# Main.net
KiCad netlist of a schematic drawn in Altium Designer
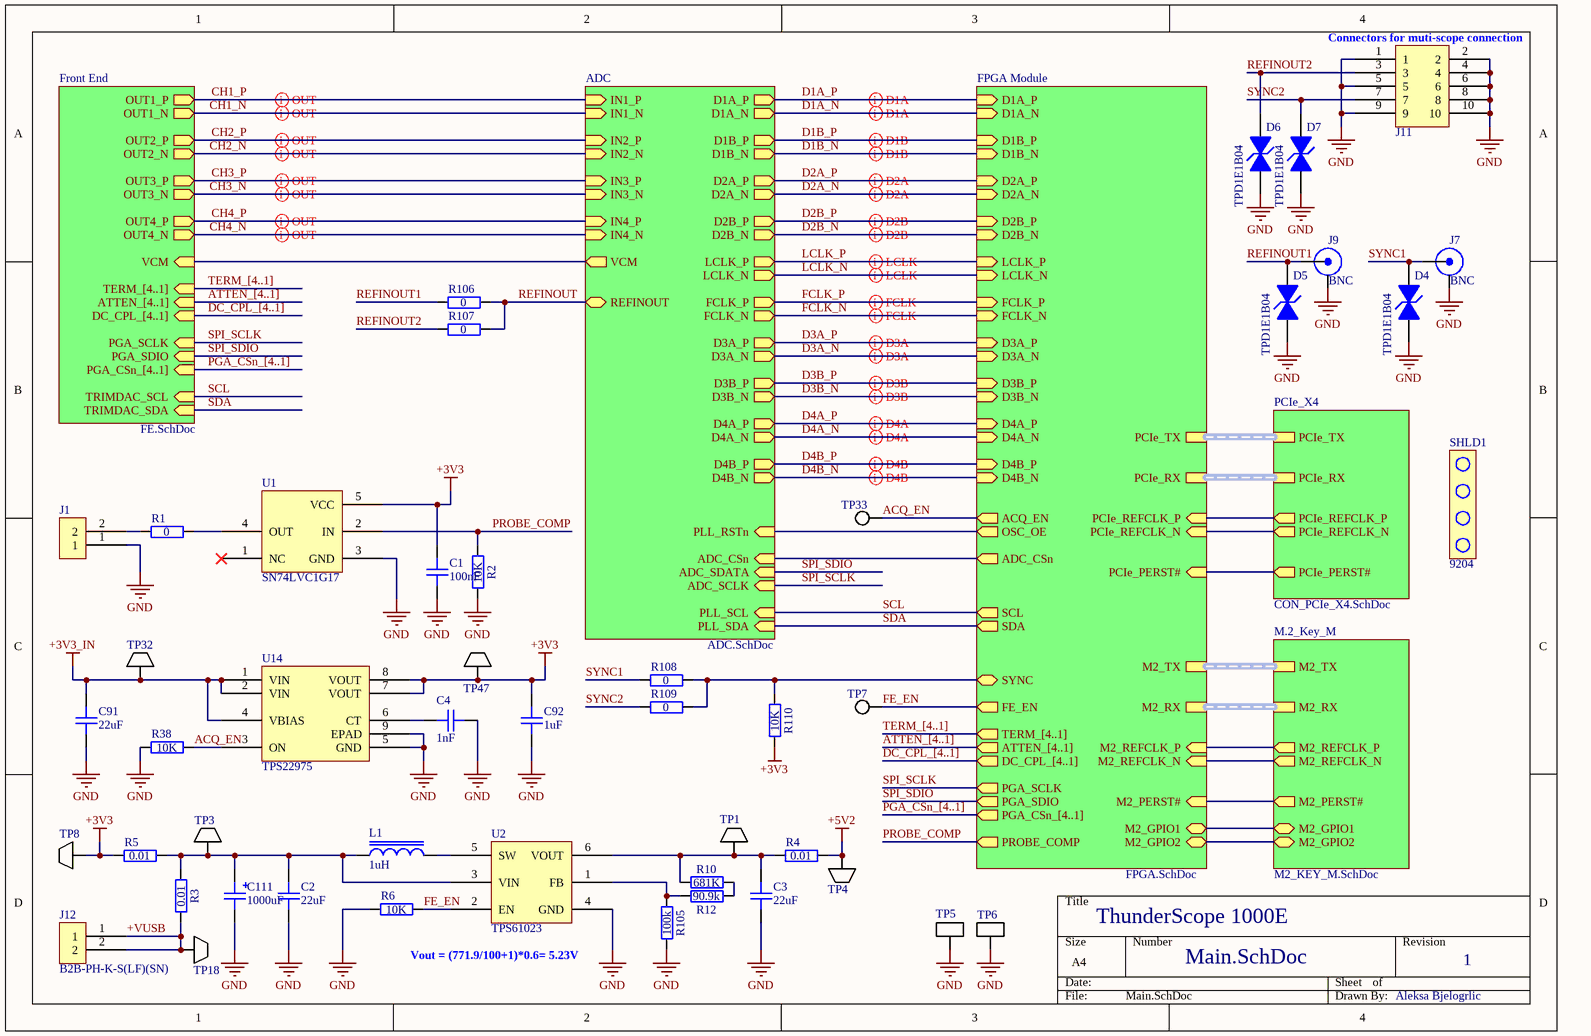
[diagram p0: Main.SchDoc]

(export (version "E")
  (design (tool "Eeschema 10.0.6"))
  (components
    (comp (ref "C1")
      (value "100nF")
      (footprint "GEN_C_0402")
      (libsource (lib "DSO") (part "CAP 100nF 16V X7R 0402"))
    )
    (comp (ref "C2")
      (value "22uF")
      (footprint "GEN_C_0805")
      (libsource (lib "DSO") (part "CAP 22uF 25V X5R 0805"))
    )
    (comp (ref "C3")
      (value "22uF")
      (footprint "GEN_C_0805")
      (libsource (lib "DSO") (part "CAP 22uF 25V X5R 0805"))
    )
    (comp (ref "C4")
      (value "1nF")
      (footprint "GEN_C_0402")
      (libsource (lib "DSO") (part "CAP 1nF 50V C0G 0402"))
    )
    (comp (ref "C91")
      (value "22uF")
      (footprint "GEN_C_0805")
      (libsource (lib "DSO") (part "CAP 22uF 25V X5R 0805"))
    )
    (comp (ref "C92")
      (value "1uF")
      (footprint "GEN_C_0402")
      (libsource (lib "DSO") (part "CAP 1uF 25V X5R 0402"))
    )
    (comp (ref "C111")
      (value "1000uF")
      (footprint "GEN_C_POLAR_10mm")
      (libsource (lib "DSO") (part "CAP 1000uF 16V 10mm Dia"))
    )
    (comp (ref "D4")
      (value "TPD1E1B04")
      (footprint "TI_X1SON_DPY0002A")
      (libsource (lib "DSO") (part "TVS TPD1E1B04"))
    )
    (comp (ref "D5")
      (value "TPD1E1B04")
      (footprint "TI_X1SON_DPY0002A")
      (libsource (lib "DSO") (part "TVS TPD1E1B04"))
    )
    (comp (ref "D6")
      (value "TPD1E1B04")
      (footprint "TI_X1SON_DPY0002A")
      (libsource (lib "DSO") (part "TVS TPD1E1B04"))
    )
    (comp (ref "D7")
      (value "TPD1E1B04")
      (footprint "TI_X1SON_DPY0002A")
      (libsource (lib "DSO") (part "TVS TPD1E1B04"))
    )
    (comp (ref "J1")
      (value "TSW-101-08-F-D-RA")
      (footprint "GEN_2.54mm_1x2_Pin_TH_RA")
      (libsource (lib "DSO") (part "CONN 2.54mm 2 Pin TH RA"))
    )
    (comp (ref "J7") (value "BNC") (footprint "MOL_0731000105") (libsource (lib "DSO") (part "BNC JACK R/A")))
    (comp (ref "J9") (value "BNC") (footprint "MOL_0731000105") (libsource (lib "DSO") (part "BNC JACK R/A")))
    (comp (ref "J11")
      (value "1.27mm 6 Pin TH")
      (footprint "GEN_1.27mm_2x5_Pin_TH_RA")
      (libsource (lib "DSO") (part "CONN 1.27mm 2x5 Pin TH RA"))
    )
    (comp (ref "J12")
      (value "B2B-PH-K-S(LF)(SN)")
      (footprint "JST_B2B-PH-K-S(LF)(SN)")
      (libsource (lib "DSO") (part "CONN JST PH 2 Pin TH"))
    )
    (comp (ref "L1")
      (value "1uH")
      (footprint "GEN_L_1210")
      (libsource (lib "DSO") (part "IND 1uH 3.1A 45 MOHM 1210"))
    )
    (comp (ref "R1")
      (value "0")
      (footprint "GEN_R_0402")
      (libsource (lib "DSO") (part "RES 0 OHM 1/16W 0402"))
    )
    (comp (ref "R2")
      (value "10K")
      (footprint "GEN_R_0402")
      (fields (field (name "TOLERANCE") "1%"))
      (libsource (lib "DSO") (part "RES 10K OHM 1% 1/10W 0402"))
    )
    (comp (ref "R3")
      (value "0.01")
      (footprint "GEN_R_0603")
      (fields (field (name "TOLERANCE") "1%"))
      (libsource (lib "") (part "RES 0.01 OHM 1% 1/4W 0603_1"))
    )
    (comp (ref "R4")
      (value "0.01")
      (footprint "GEN_R_0603")
      (fields (field (name "TOLERANCE") "1%"))
      (libsource (lib "DSO") (part "RES 0.01 OHM 1% 1/4W 0603"))
    )
    (comp (ref "R5")
      (value "0.01")
      (footprint "GEN_R_0603")
      (fields (field (name "TOLERANCE") "1%"))
      (libsource (lib "") (part "RES 0.01 OHM 1% 1/4W 0603_2"))
    )
    (comp (ref "R6")
      (value "10K")
      (footprint "GEN_R_0402")
      (fields (field (name "TOLERANCE") "1%"))
      (libsource (lib "") (part "RES 10K OHM 1% 1/10W 0402_1"))
    )
    (comp (ref "R10")
      (value "681K")
      (footprint "GEN_R_0402")
      (fields (field (name "TOLERANCE") "1%"))
      (libsource (lib "DSO") (part "RES 681K OHM 1% 1/16W 0402"))
    )
    (comp (ref "R12")
      (value "90.9k")
      (footprint "GEN_R_0402")
      (fields (field (name "TOLERANCE") "1%"))
      (libsource (lib "DSO") (part "RES 90.9K OHM 1% 1/16W 0402"))
    )
    (comp (ref "R38")
      (value "10K")
      (footprint "GEN_R_0402")
      (fields (field (name "TOLERANCE") "1%"))
      (libsource (lib "DSO") (part "RES 10K OHM 1% 1/10W 0402"))
    )
    (comp (ref "R105")
      (value "100k")
      (footprint "GEN_R_0402")
      (fields (field (name "TOLERANCE") "1%"))
      (libsource (lib "DSO") (part "RES 100K OHM 1% 1/10W 0402"))
    )
    (comp (ref "R106")
      (value "0")
      (footprint "GEN_R_0402")
      (libsource (lib "DSO") (part "RES 0 OHM 1/16W 0402"))
    )
    (comp (ref "R107")
      (value "0")
      (footprint "GEN_R_0402")
      (libsource (lib "DSO") (part "RES 0 OHM 1/16W 0402"))
    )
    (comp (ref "R108")
      (value "0")
      (footprint "GEN_R_0402")
      (libsource (lib "DSO") (part "RES 0 OHM 1/16W 0402"))
    )
    (comp (ref "R109")
      (value "0")
      (footprint "GEN_R_0402")
      (libsource (lib "DSO") (part "RES 0 OHM 1/16W 0402"))
    )
    (comp (ref "R110")
      (value "10K")
      (footprint "GEN_R_0402")
      (fields (field (name "TOLERANCE") "1%"))
      (libsource (lib "DSO") (part "RES 10K OHM 1% 1/10W 0402"))
    )
    (comp (ref "SHLD1") (value "9204") (libsource (lib "DSO") (part "PCIe IO Shield")))
    (comp (ref "TP1") (value "5015") (footprint "KEY_5015") (libsource (lib "DSO") (part "TP KEYSTONE 5015")))
    (comp (ref "TP3") (value "5015") (footprint "KEY_5015") (libsource (lib "DSO") (part "TP KEYSTONE 5015")))
    (comp (ref "TP4") (value "5015") (footprint "KEY_5015") (libsource (lib "DSO") (part "TP KEYSTONE 5015")))
    (comp (ref "TP5") (value "5019") (footprint "KEY_5019") (libsource (lib "DSO") (part "TP KEYSTONE 5019")))
    (comp (ref "TP6") (value "5019") (footprint "KEY_5019") (libsource (lib "DSO") (part "TP KEYSTONE 5019")))
    (comp (ref "TP7") (value "PCB") (footprint "GEN_TP_PCB") (libsource (lib "DSO") (part "TP PCB 1mm")))
    (comp (ref "TP8") (value "5015") (footprint "KEY_5015") (libsource (lib "DSO") (part "TP KEYSTONE 5015")))
    (comp (ref "TP18")
      (value "5015")
      (footprint "KEY_5015")
      (libsource (lib "DSO") (part "TP KEYSTONE 5015"))
    )
    (comp (ref "TP32")
      (value "5015")
      (footprint "KEY_5015")
      (libsource (lib "DSO") (part "TP KEYSTONE 5015"))
    )
    (comp (ref "TP33") (value "PCB") (footprint "GEN_TP_PCB") (libsource (lib "DSO") (part "TP PCB 1mm")))
    (comp (ref "TP47")
      (value "5015")
      (footprint "KEY_5015")
      (libsource (lib "DSO") (part "TP KEYSTONE 5015"))
    )
    (comp (ref "U1")
      (value "SN74LVC1G17")
      (footprint "GEN_SC-70-5")
      (libsource (lib "DSO") (part "IC BUFFER SN74LVC1G17"))
    )
    (comp (ref "U2")
      (value "TPS61023")
      (footprint "TI_SOT563_DRL0006A")
      (libsource (lib "DSO") (part "IC BOOST TPS61023"))
    )
    (comp (ref "U14")
      (value "TPS22975")
      (footprint "TI_WSON8_DSG0008A")
      (libsource (lib "DSO") (part "IC SWITCH LOAD TPS22975"))
    )
  )
  (nets
    (net (code "17") (name "+3V3") (class "Default")
      (node (ref "C1") (pin "1") (pinfunction "1_1") (pintype "passive"))
      (node (ref "C92") (pin "2") (pinfunction "2_2") (pintype "passive"))
      (node (ref "R110") (pin "1") (pinfunction "1_1") (pintype "passive"))
      (node (ref "R5") (pin "2") (pinfunction "2_2") (pintype "passive"))
      (node (ref "TP47") (pin "1") (pinfunction "1_1") (pintype "passive"))
      (node (ref "TP8") (pin "1") (pinfunction "1_1") (pintype "passive"))
      (node (ref "U1") (pin "5") (pinfunction "VCC_5") (pintype "passive"))
      (node (ref "U14") (pin "7") (pinfunction "VOUT_7") (pintype "passive"))
      (node (ref "U14") (pin "8") (pinfunction "VOUT_8") (pintype "passive"))
    )
    (net (code "18") (name "+3V3_IN") (class "Default")
      (node (ref "C91") (pin "2") (pinfunction "2_2") (pintype "passive"))
      (node (ref "TP32") (pin "1") (pinfunction "1_1") (pintype "passive"))
      (node (ref "U14") (pin "1") (pinfunction "VIN_1") (pintype "passive"))
      (node (ref "U14") (pin "2") (pinfunction "VIN_2") (pintype "passive"))
      (node (ref "U14") (pin "4") (pinfunction "VBIAS_4") (pintype "passive"))
    )
    (net (code "19") (name "+5V2") (class "Default")
      (node (ref "R4") (pin "2") (pinfunction "2_2") (pintype "passive"))
      (node (ref "TP4") (pin "1") (pinfunction "1_1") (pintype "passive"))
    )
    (net (code "20") (name "/+VUSB") (class "Default")
      (node (ref "J12") (pin "1") (pinfunction "1_1") (pintype "passive"))
      (node (ref "J12") (pin "2") (pinfunction "2_2") (pintype "passive"))
      (node (ref "R3") (pin "2") (pinfunction "2_2") (pintype "passive"))
      (node (ref "TP18") (pin "1") (pinfunction "1_1") (pintype "passive"))
    )
    (net (code "21") (name "/ACQ_EN") (class "Default")
      (node (ref "R38") (pin "2") (pinfunction "2_2") (pintype "passive"))
      (node (ref "TP33") (pin "1") (pinfunction "1_1") (pintype "passive"))
      (node (ref "U14") (pin "3") (pinfunction "ON_3") (pintype "passive"))
    )
    (net (code "51") (name "/FE_EN") (class "Default")
      (node (ref "R6") (pin "1") (pinfunction "1_1") (pintype "passive"))
      (node (ref "TP7") (pin "1") (pinfunction "1_1") (pintype "passive"))
      (node (ref "U2") (pin "2") (pinfunction "EN_2") (pintype "passive"))
    )
    (net (code "68") (name "/PROBE_COMP") (class "Default")
      (node (ref "R2") (pin "2") (pinfunction "2_2") (pintype "passive"))
      (node (ref "U1") (pin "2") (pinfunction "IN_2") (pintype "passive"))
    )
    (net (code "69") (name "/REFINOUT") (class "Default")
      (node (ref "R106") (pin "2") (pinfunction "2_2") (pintype "passive"))
      (node (ref "R107") (pin "2") (pinfunction "2_2") (pintype "passive"))
    )
    (net (code "70") (name "/REFINOUT1") (class "Default")
      (node (ref "D5") (pin "1") (pinfunction "K_1") (pintype "passive"))
      (node (ref "J9") (pin "1") (pinfunction "Signal_1") (pintype "passive"))
      (node (ref "R106") (pin "1") (pinfunction "1_1") (pintype "passive"))
    )
    (net (code "71") (name "/REFINOUT2") (class "Default")
      (node (ref "D6") (pin "1") (pinfunction "K_1") (pintype "passive"))
      (node (ref "J11") (pin "3") (pinfunction "3_3") (pintype "passive"))
      (node (ref "R107") (pin "1") (pinfunction "1_1") (pintype "passive"))
    )
    (net (code "76") (name "/SYNC") (class "Default")
      (node (ref "R108") (pin "2") (pinfunction "2_2") (pintype "passive"))
      (node (ref "R109") (pin "2") (pinfunction "2_2") (pintype "passive"))
      (node (ref "R110") (pin "2") (pinfunction "2_2") (pintype "passive"))
    )
    (net (code "77") (name "/SYNC1") (class "Default")
      (node (ref "D4") (pin "1") (pinfunction "K_1") (pintype "passive"))
      (node (ref "J7") (pin "1") (pinfunction "Signal_1") (pintype "passive"))
      (node (ref "R108") (pin "1") (pinfunction "1_1") (pintype "passive"))
    )
    (net (code "78") (name "/SYNC2") (class "Default")
      (node (ref "D7") (pin "1") (pinfunction "K_1") (pintype "passive"))
      (node (ref "J11") (pin "7") (pinfunction "7_7") (pintype "passive"))
      (node (ref "R109") (pin "1") (pinfunction "1_1") (pintype "passive"))
    )
    (net (code "81") (name "GND") (class "Default")
      (node (ref "C1") (pin "2") (pinfunction "2_2") (pintype "passive"))
      (node (ref "C111") (pin "2") (pinfunction "2_2") (pintype "passive"))
      (node (ref "C2") (pin "1") (pinfunction "1_1") (pintype "passive"))
      (node (ref "C3") (pin "1") (pinfunction "1_1") (pintype "passive"))
      (node (ref "C4") (pin "1") (pinfunction "1_1") (pintype "passive"))
      (node (ref "C91") (pin "1") (pinfunction "1_1") (pintype "passive"))
      (node (ref "C92") (pin "1") (pinfunction "1_1") (pintype "passive"))
      (node (ref "D4") (pin "2") (pinfunction "A_2") (pintype "passive"))
      (node (ref "D5") (pin "2") (pinfunction "A_2") (pintype "passive"))
      (node (ref "D6") (pin "2") (pinfunction "A_2") (pintype "passive"))
      (node (ref "D7") (pin "2") (pinfunction "A_2") (pintype "passive"))
      (node (ref "J1") (pin "1") (pinfunction "1_1") (pintype "passive"))
      (node (ref "J11") (pin "1") (pinfunction "1_1") (pintype "passive"))
      (node (ref "J11") (pin "10") (pinfunction "10_10") (pintype "passive"))
      (node (ref "J11") (pin "2") (pinfunction "2_2") (pintype "passive"))
      (node (ref "J11") (pin "4") (pinfunction "4_4") (pintype "passive"))
      (node (ref "J11") (pin "5") (pinfunction "5_5") (pintype "passive"))
      (node (ref "J11") (pin "6") (pinfunction "6_6") (pintype "passive"))
      (node (ref "J11") (pin "8") (pinfunction "8_8") (pintype "passive"))
      (node (ref "J11") (pin "9") (pinfunction "9_9") (pintype "passive"))
      (node (ref "J7") (pin "2") (pinfunction "SHIELD_2") (pintype "passive"))
      (node (ref "J9") (pin "2") (pinfunction "SHIELD_2") (pintype "passive"))
      (node (ref "R105") (pin "1") (pinfunction "1_1") (pintype "passive"))
      (node (ref "R2") (pin "1") (pinfunction "1_1") (pintype "passive"))
      (node (ref "R38") (pin "1") (pinfunction "1_1") (pintype "passive"))
      (node (ref "R6") (pin "2") (pinfunction "2_2") (pintype "passive"))
      (node (ref "TP5") (pin "1") (pinfunction "1_1") (pintype "passive"))
      (node (ref "TP6") (pin "1") (pinfunction "1_1") (pintype "passive"))
      (node (ref "U1") (pin "3") (pinfunction "GND_3") (pintype "passive"))
      (node (ref "U14") (pin "5") (pinfunction "GND_5") (pintype "passive"))
      (node (ref "U14") (pin "9") (pinfunction "EPAD_9") (pintype "passive"))
      (node (ref "U2") (pin "4") (pinfunction "GND_4") (pintype "power_in"))
    )
    (net (code "82") (name "Net-(J1-Pad2)") (class "Default")
      (node (ref "J1") (pin "2") (pinfunction "2_2") (pintype "passive"))
      (node (ref "R1") (pin "1") (pinfunction "1_1") (pintype "passive"))
    )
    (net (code "83") (name "Net-(R10-Pad1)") (class "Default")
      (node (ref "R10") (pin "1") (pinfunction "1_1") (pintype "passive"))
      (node (ref "R12") (pin "2") (pinfunction "2_2") (pintype "passive"))
    )
    (net (code "84") (name "Net-(U1-OUT)") (class "Default")
      (node (ref "R1") (pin "2") (pinfunction "2_2") (pintype "passive"))
      (node (ref "U1") (pin "4") (pinfunction "OUT_4") (pintype "passive"))
    )
    (net (code "85") (name "Net-(U2-FB)") (class "Default")
      (node (ref "R105") (pin "2") (pinfunction "2_2") (pintype "passive"))
      (node (ref "R12") (pin "1") (pinfunction "1_1") (pintype "passive"))
      (node (ref "U2") (pin "1") (pinfunction "FB_1") (pintype "passive"))
    )
    (net (code "86") (name "Net-(U2-SW)") (class "Default")
      (node (ref "L1") (pin "2") (pinfunction "2_2") (pintype "passive"))
      (node (ref "U2") (pin "5") (pinfunction "SW_5") (pintype "passive"))
    )
    (net (code "87") (name "Net-(U2-VIN)") (class "Default")
      (node (ref "C111") (pin "1") (pinfunction "1_1") (pintype "passive"))
      (node (ref "C2") (pin "2") (pinfunction "2_2") (pintype "passive"))
      (node (ref "L1") (pin "1") (pinfunction "1_1") (pintype "passive"))
      (node (ref "R3") (pin "1") (pinfunction "1_1") (pintype "passive"))
      (node (ref "R5") (pin "1") (pinfunction "1_1") (pintype "passive"))
      (node (ref "TP3") (pin "1") (pinfunction "1_1") (pintype "passive"))
      (node (ref "U2") (pin "3") (pinfunction "VIN_3") (pintype "power_in"))
    )
    (net (code "88") (name "Net-(U2-VOUT)") (class "Default")
      (node (ref "C3") (pin "2") (pinfunction "2_2") (pintype "passive"))
      (node (ref "R10") (pin "2") (pinfunction "2_2") (pintype "passive"))
      (node (ref "R4") (pin "1") (pinfunction "1_1") (pintype "passive"))
      (node (ref "TP1") (pin "1") (pinfunction "1_1") (pintype "passive"))
      (node (ref "U2") (pin "6") (pinfunction "VOUT_6") (pintype "passive"))
    )
    (net (code "89") (name "Net-(U14-CT)") (class "Default")
      (node (ref "C4") (pin "2") (pinfunction "2_2") (pintype "passive"))
      (node (ref "U14") (pin "6") (pinfunction "CT_6") (pintype "passive"))
    )
    (net (code "90") (name "unconnected-(U1-NC-Pad1)") (class "Default")
      (node (ref "U1") (pin "1") (pinfunction "NC_1") (pintype "passive+no_connect"))
    )
  )
)
